# harp_camera_controller_v_1_0.net
KiCad netlist of a schematic drawn in EAGLE
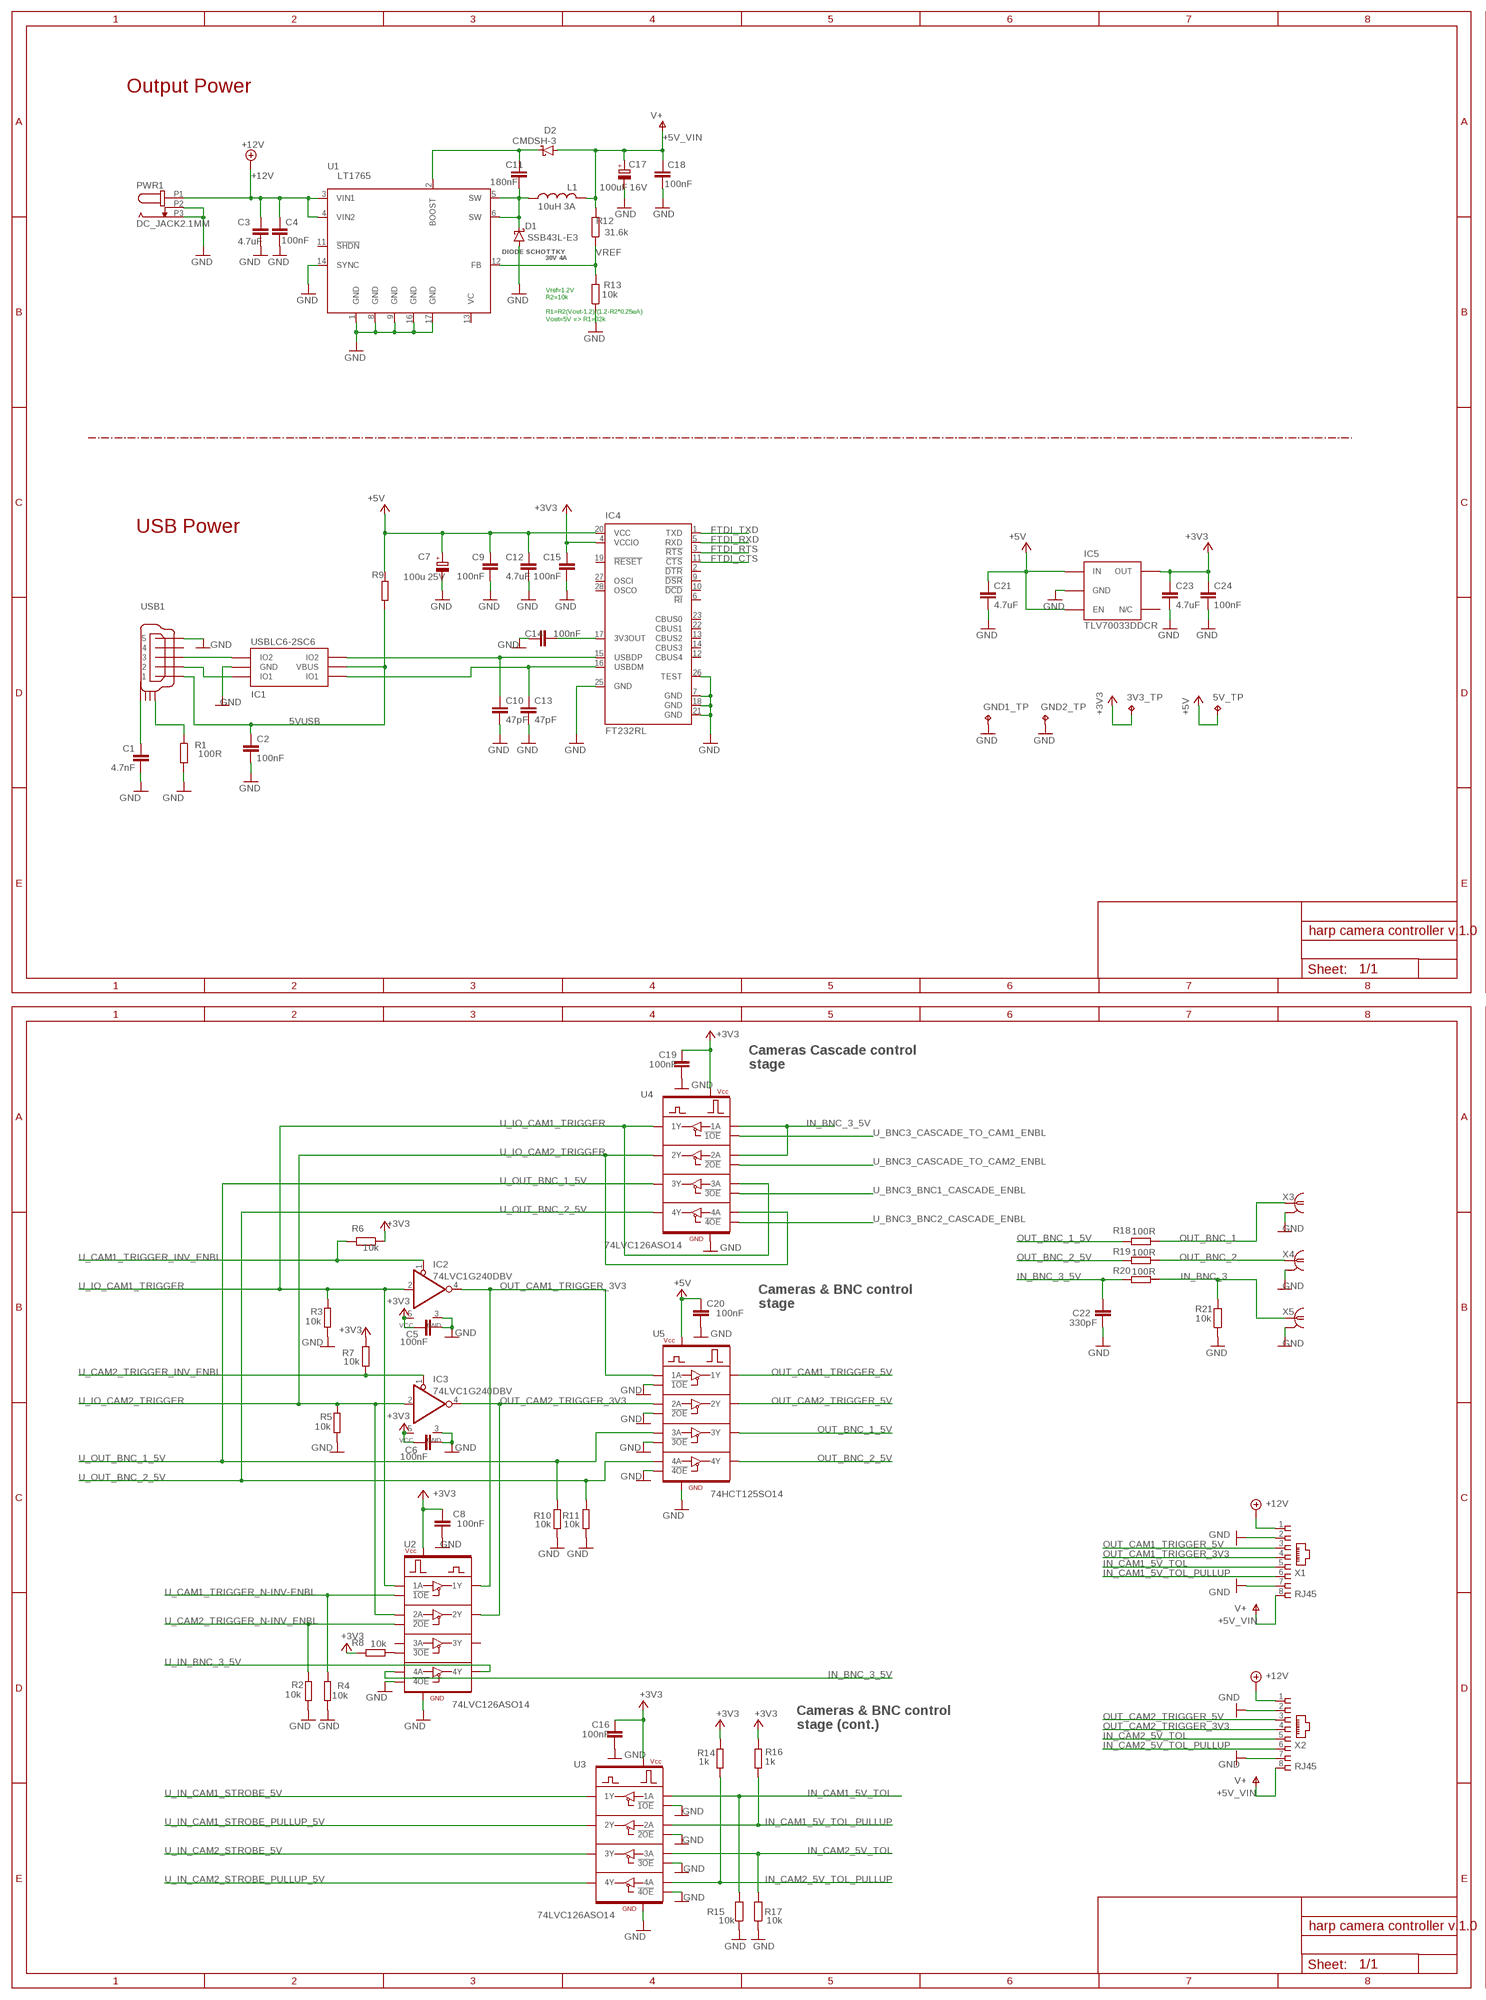
[diagram p0: schematic, sheet 1, part 1 of 2]
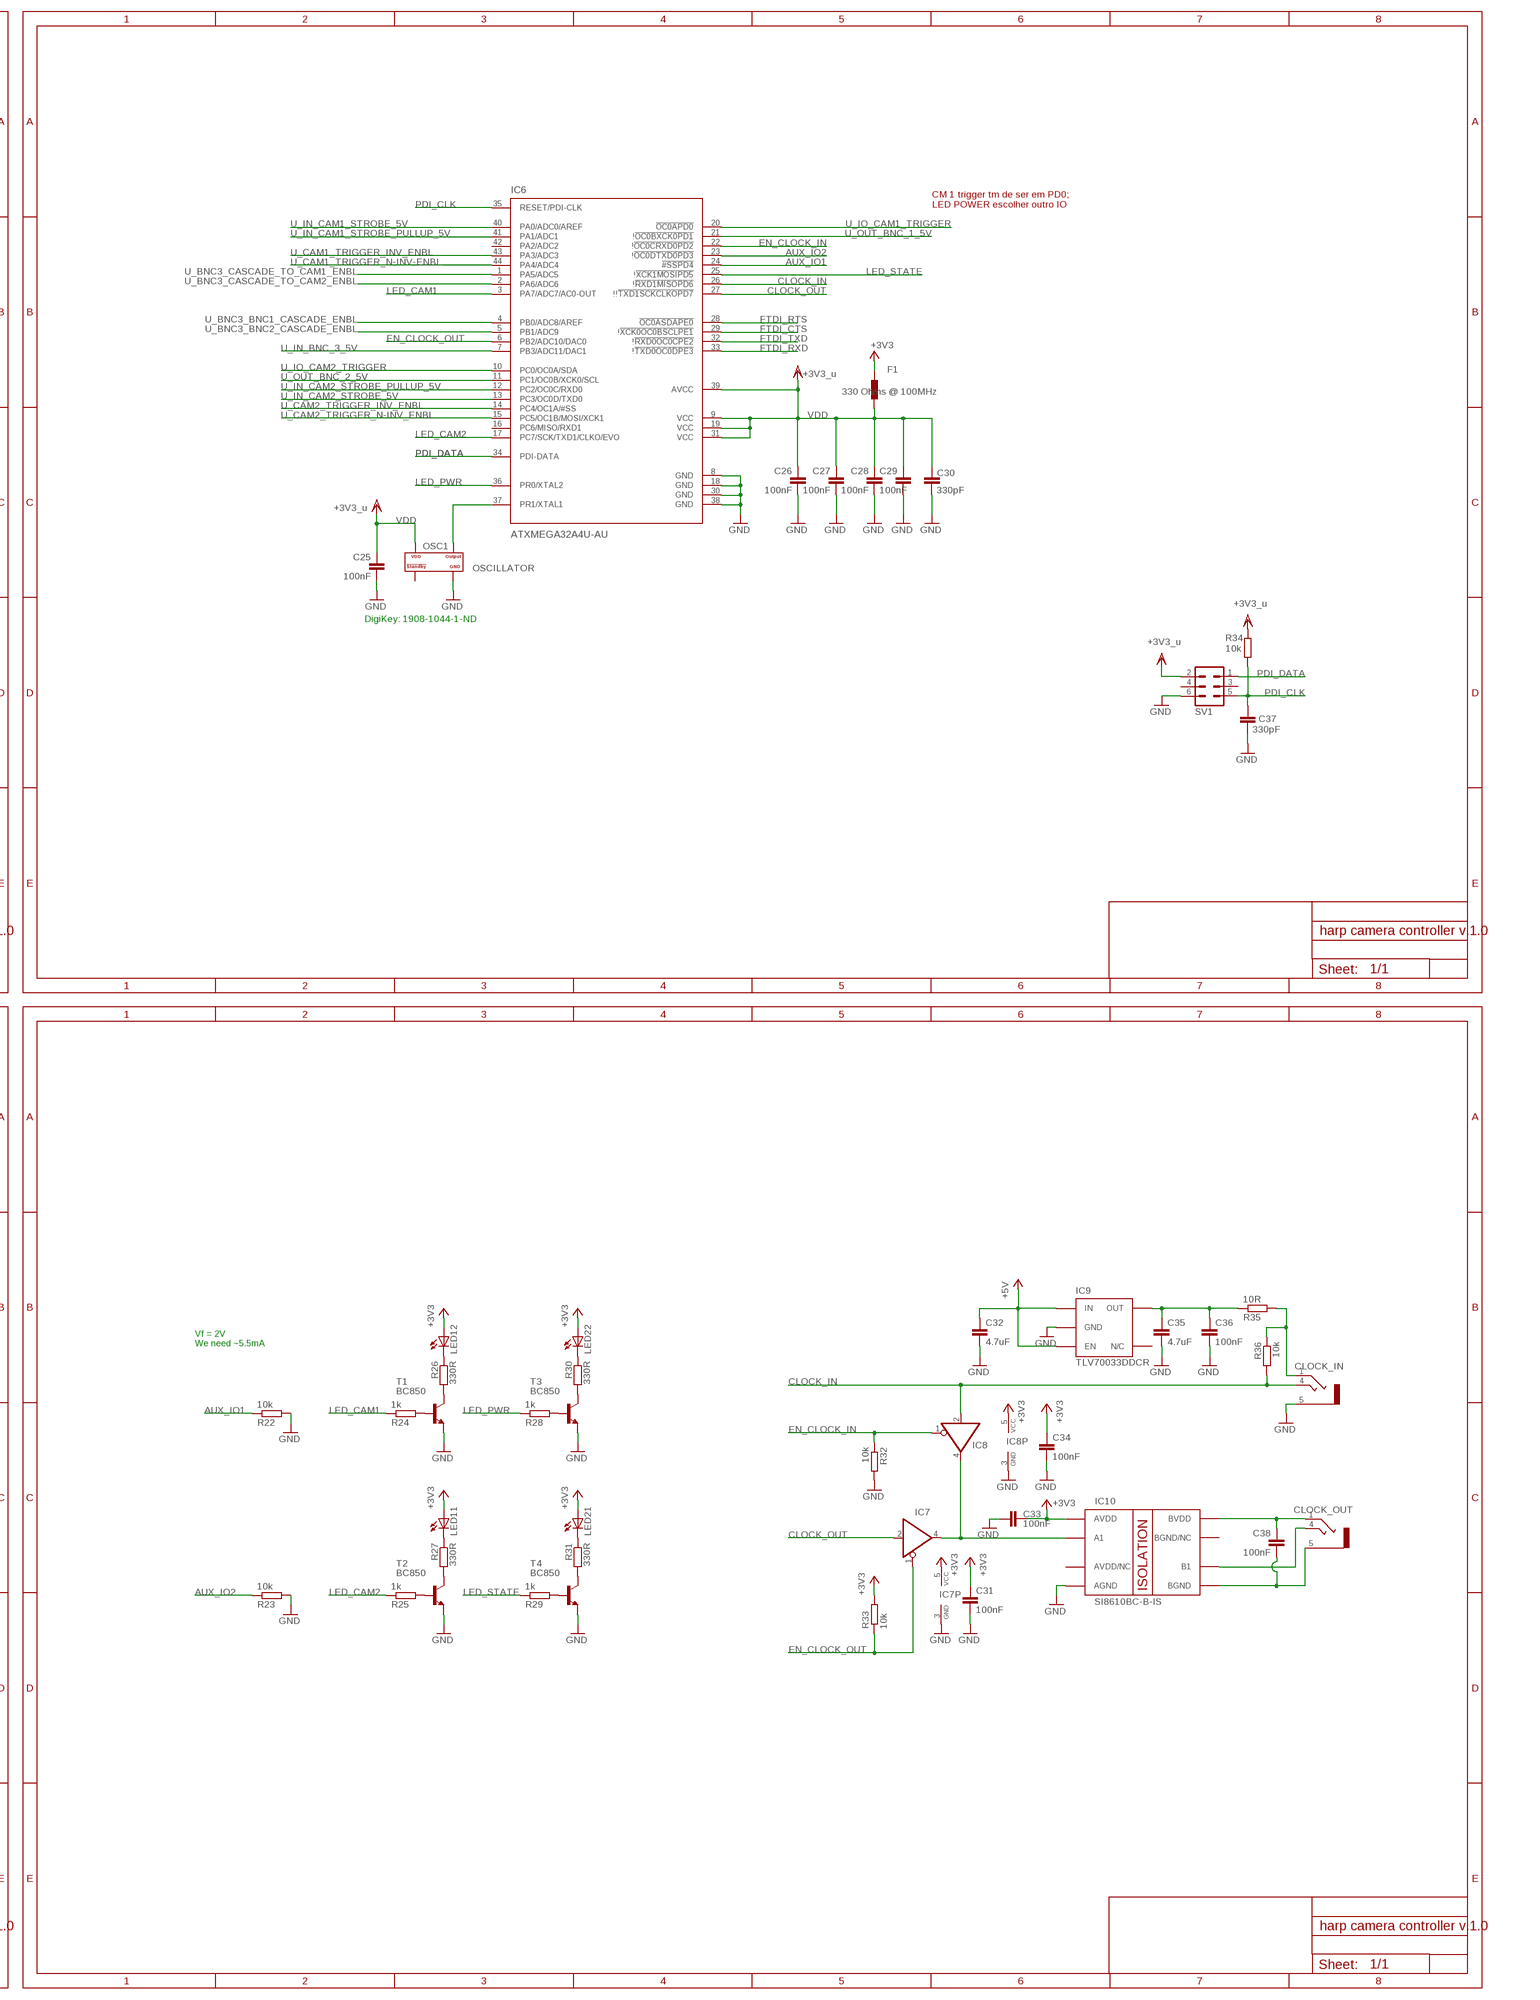
[diagram p1: schematic, sheet 1, part 2 of 2]

(export (version "E")
  (design (tool "Eeschema 10.0.6"))
  (components
    (comp (ref "3V3_TP")
      (value "TPPAD1-13")
      (footprint "eagle-import:P1-13")
      (fields (field (name "MPN") "N.A."))
      (libsource (lib "eagle-import") (part "TPPAD1-13"))
    )
    (comp (ref "5V_TP")
      (value "TPPAD1-13")
      (footprint "eagle-import:P1-13")
      (fields (field (name "MPN") "N.A."))
      (libsource (lib "eagle-import") (part "TPPAD1-13"))
    )
    (comp (ref "C1")
      (value "4.7nF")
      (footprint "eagle-import:C0402")
      (fields (field (name "MPN") "885012205084  "))
      (libsource (lib "eagle-import") (part "C-EUC0402"))
    )
    (comp (ref "C2")
      (value "100nF")
      (footprint "eagle-import:C0402")
      (fields (field (name "MPN") "C1005X7R1H104K050BB"))
      (libsource (lib "eagle-import") (part "C-EUC0402"))
    )
    (comp (ref "C3")
      (value "4.7uF")
      (footprint "eagle-import:C0805")
      (fields (field (name "MPN") "CL21A475KLCLQNC"))
      (libsource (lib "eagle-import") (part "C-EUC0805"))
    )
    (comp (ref "C4")
      (value "100nF")
      (footprint "eagle-import:C0402")
      (fields (field (name "MPN") "C1005X7R1H104K050BB"))
      (libsource (lib "eagle-import") (part "C-EUC0402"))
    )
    (comp (ref "C5")
      (value "100nF")
      (footprint "eagle-import:C0402")
      (fields (field (name "MPN") "C1005X7R1H104K050BB"))
      (libsource (lib "eagle-import") (part "C-EUC0402"))
    )
    (comp (ref "C6")
      (value "100nF")
      (footprint "eagle-import:C0402")
      (fields (field (name "MPN") "C1005X7R1H104K050BB"))
      (libsource (lib "eagle-import") (part "C-EUC0402"))
    )
    (comp (ref "C7")
      (value "100u 25V")
      (footprint "eagle-import:TT2D6")
      (fields (field (name "MPN") "EEU-FM1E101B"))
      (libsource (lib "eagle-import") (part "CPOL-EUTT2D6"))
    )
    (comp (ref "C8")
      (value "100nF")
      (footprint "eagle-import:C0402")
      (fields (field (name "MPN") "C1005X7R1H104K050BB"))
      (libsource (lib "eagle-import") (part "C-EUC0402"))
    )
    (comp (ref "C9")
      (value "100nF")
      (footprint "eagle-import:C0402")
      (fields (field (name "MPN") "C1005X7R1H104K050BB"))
      (libsource (lib "eagle-import") (part "C-EUC0402"))
    )
    (comp (ref "C10")
      (value "47pF")
      (footprint "eagle-import:C0402")
      (fields (field (name "MPN") "04025A470JAT2A"))
      (libsource (lib "eagle-import") (part "C-EUC0402"))
    )
    (comp (ref "C11")
      (value "180nF")
      (footprint "eagle-import:C0603")
      (fields (field (name "MPN") "GCG188R91H184KA01D"))
      (libsource (lib "eagle-import") (part "C-EUC0603"))
    )
    (comp (ref "C12")
      (value "4.7uF")
      (footprint "eagle-import:C0603")
      (fields (field (name "MPN") "C1608X6S1C475K080AC"))
      (libsource (lib "eagle-import") (part "C-EUC0603"))
    )
    (comp (ref "C13")
      (value "47pF")
      (footprint "eagle-import:C0402")
      (fields (field (name "MPN") "04025A470JAT2A"))
      (libsource (lib "eagle-import") (part "C-EUC0402"))
    )
    (comp (ref "C14")
      (value "100nF")
      (footprint "eagle-import:C0402")
      (fields (field (name "MPN") "C1005X7R1H104K050BB"))
      (libsource (lib "eagle-import") (part "C-EUC0402"))
    )
    (comp (ref "C15")
      (value "100nF")
      (footprint "eagle-import:C0402")
      (fields (field (name "MPN") "C1005X7R1H104K050BB"))
      (libsource (lib "eagle-import") (part "C-EUC0402"))
    )
    (comp (ref "C16")
      (value "100nF")
      (footprint "eagle-import:C0402")
      (fields (field (name "MPN") "C1005X7R1H104K050BB"))
      (libsource (lib "eagle-import") (part "C-EUC0402"))
    )
    (comp (ref "C17")
      (value "100uF 16V")
      (footprint "eagle-import:CT7343")
      (fields (field (name "MPN") "T491D107K016AT7280"))
      (libsource (lib "eagle-import") (part "CPOL-EUCT7343"))
    )
    (comp (ref "C18")
      (value "100nF")
      (footprint "eagle-import:C0402")
      (fields (field (name "MPN") "C1005X7R1H104K050BB"))
      (libsource (lib "eagle-import") (part "C-EUC0402"))
    )
    (comp (ref "C19")
      (value "100nF")
      (footprint "eagle-import:C0402")
      (fields (field (name "MPN") "C1005X7R1H104K050BB"))
      (libsource (lib "eagle-import") (part "C-EUC0402"))
    )
    (comp (ref "C20")
      (value "100nF")
      (footprint "eagle-import:C0402")
      (fields (field (name "MPN") "C1005X7R1H104K050BB"))
      (libsource (lib "eagle-import") (part "C-EUC0402"))
    )
    (comp (ref "C21")
      (value "4.7uF")
      (footprint "eagle-import:C0603")
      (fields (field (name "MPN") "C1608X6S1C475K080AC"))
      (libsource (lib "eagle-import") (part "C-EUC0603"))
    )
    (comp (ref "C22")
      (value "330pF")
      (footprint "eagle-import:C0402")
      (fields (field (name "MPN") "C0402C331J5GACTU"))
      (libsource (lib "eagle-import") (part "C-EUC0402"))
    )
    (comp (ref "C23")
      (value "4.7uF")
      (footprint "eagle-import:C0603")
      (fields (field (name "MPN") "C1608X6S1C475K080AC"))
      (libsource (lib "eagle-import") (part "C-EUC0603"))
    )
    (comp (ref "C24")
      (value "100nF")
      (footprint "eagle-import:C0402")
      (fields (field (name "MPN") "C1005X7R1H104K050BB"))
      (libsource (lib "eagle-import") (part "C-EUC0402"))
    )
    (comp (ref "C25")
      (value "100nF")
      (footprint "eagle-import:C0402")
      (fields (field (name "MPN") "C1005X7R1H104K050BB"))
      (libsource (lib "eagle-import") (part "C-EUC0402"))
    )
    (comp (ref "C26")
      (value "100nF")
      (footprint "eagle-import:C0402")
      (fields (field (name "MPN") "C1005X7R1H104K050BB"))
      (libsource (lib "eagle-import") (part "C-EUC0402"))
    )
    (comp (ref "C27")
      (value "100nF")
      (footprint "eagle-import:C0402")
      (fields (field (name "MPN") "C1005X7R1H104K050BB"))
      (libsource (lib "eagle-import") (part "C-EUC0402"))
    )
    (comp (ref "C28")
      (value "100nF")
      (footprint "eagle-import:C0402")
      (fields (field (name "MPN") "C1005X7R1H104K050BB"))
      (libsource (lib "eagle-import") (part "C-EUC0402"))
    )
    (comp (ref "C29")
      (value "100nF")
      (footprint "eagle-import:C0402")
      (fields (field (name "MPN") "C1005X7R1H104K050BB"))
      (libsource (lib "eagle-import") (part "C-EUC0402"))
    )
    (comp (ref "C30")
      (value "330pF")
      (footprint "eagle-import:C0402")
      (fields (field (name "MPN") "C0402C331J5GACTU"))
      (libsource (lib "eagle-import") (part "C-EUC0402"))
    )
    (comp (ref "C31")
      (value "100nF")
      (footprint "eagle-import:C0402")
      (fields (field (name "MPN") "C1005X7R1H104K050BB"))
      (libsource (lib "eagle-import") (part "C-EUC0402"))
    )
    (comp (ref "C32")
      (value "4.7uF")
      (footprint "eagle-import:C0603")
      (fields (field (name "MPN") "C1608X6S1C475K080AC"))
      (libsource (lib "eagle-import") (part "C-EUC0603"))
    )
    (comp (ref "C33")
      (value "100nF")
      (footprint "eagle-import:C0402")
      (fields (field (name "MPN") "C1005X7R1H104K050BB"))
      (libsource (lib "eagle-import") (part "C-EUC0402"))
    )
    (comp (ref "C34")
      (value "100nF")
      (footprint "eagle-import:C0402")
      (fields (field (name "MPN") "C1005X7R1H104K050BB"))
      (libsource (lib "eagle-import") (part "C-EUC0402"))
    )
    (comp (ref "C35")
      (value "4.7uF")
      (footprint "eagle-import:C0603")
      (fields (field (name "MPN") "C1608X6S1C475K080AC"))
      (libsource (lib "eagle-import") (part "C-EUC0603"))
    )
    (comp (ref "C36")
      (value "100nF")
      (footprint "eagle-import:C0402")
      (fields (field (name "MPN") "C1005X7R1H104K050BB"))
      (libsource (lib "eagle-import") (part "C-EUC0402"))
    )
    (comp (ref "C37")
      (value "330pF")
      (footprint "eagle-import:C0402")
      (fields (field (name "MPN") "C0402C331J5GACTU"))
      (libsource (lib "eagle-import") (part "C-EUC0402"))
    )
    (comp (ref "C38")
      (value "100nF")
      (footprint "eagle-import:C0402")
      (fields (field (name "MPN") "C1005X7R1H104K050BB"))
      (libsource (lib "eagle-import") (part "C-EUC0402"))
    )
    (comp (ref "CLOCK_IN")
      (value "CLCK_JACK")
      (footprint "eagle-import:35RASMT2BHNTRX")
      (fields (field (name "MPN") "35RASMT2BHNTRX"))
      (libsource (lib "eagle-import") (part "STEREO_JACK"))
    )
    (comp (ref "CLOCK_OUT")
      (value "CLCK_JACK")
      (footprint "eagle-import:35RASMT2BHNTRX")
      (fields (field (name "MPN") "35RASMT2BHNTRX"))
      (libsource (lib "eagle-import") (part "STEREO_JACK"))
    )
    (comp (ref "D1")
      (value "SSB43L-E3")
      (footprint "eagle-import:SMB")
      (fields (field (name "MPN") "SSB43L-E3/52T"))
      (libsource (lib "eagle-import") (part "SCHOTTKY-DIODE"))
    )
    (comp (ref "D2")
      (value "CMDSH-3")
      (footprint "eagle-import:SOD323-R")
      (libsource (lib "eagle-import") (part "SCHOTTKY-DIODESOD323"))
    )
    (comp (ref "F1")
      (value "330 Ohms @ 100MHz")
      (footprint "eagle-import:R0603")
      (fields (field (name "MPN") "BLM18SG331TN1D"))
      (libsource (lib "eagle-import") (part "BLM15HF0603"))
    )
    (comp (ref "GND1_TP")
      (value "TPPAD1-13")
      (footprint "eagle-import:P1-13")
      (fields (field (name "MPN") "N.A."))
      (libsource (lib "eagle-import") (part "TPPAD1-13"))
    )
    (comp (ref "GND2_TP")
      (value "TPPAD1-13")
      (footprint "eagle-import:P1-13")
      (fields (field (name "MPN") "N.A."))
      (libsource (lib "eagle-import") (part "TPPAD1-13"))
    )
    (comp (ref "IC1")
      (value "USBLC6-2SC6")
      (footprint "eagle-import:SOT23-6L")
      (libsource (lib "eagle-import") (part "USBLC6-2"))
    )
    (comp (ref "IC2")
      (value "74LVC1G240DBV")
      (footprint "eagle-import:SOT23-5")
      (fields (field (name "MPN") "SN74LVC1G240DBVR"))
      (libsource (lib "eagle-import") (part "74LVC1G240DBV"))
    )
    (comp (ref "IC3")
      (value "74LVC1G240DBV")
      (footprint "eagle-import:SOT23-5")
      (fields (field (name "MPN") "SN74LVC1G240DBVR"))
      (libsource (lib "eagle-import") (part "74LVC1G240DBV"))
    )
    (comp (ref "IC4")
      (value "FT232RL")
      (footprint "eagle-import:SSOP28")
      (fields (field (name "MPN") "FT232RL-REEL"))
      (libsource (lib "eagle-import") (part "FT232RL"))
    )
    (comp (ref "IC5")
      (value "TLV70033DDCR")
      (footprint "eagle-import:TSOT23-5")
      (libsource (lib "eagle-import") (part "TLV700XX"))
    )
    (comp (ref "IC6")
      (value "ATXMEGA32A4U-AU")
      (footprint "eagle-import:QFP80P1200X1200X120-44N")
      (fields (field (name "MPN") "ATXMEGA32A4U-AUR"))
      (libsource (lib "eagle-import") (part "AT-XMEGA-XXA4-AU"))
    )
    (comp (ref "IC7")
      (value "SN74LVC1G125DBVT")
      (footprint "eagle-import:SOT23-5")
      (fields
        (field (name "DIGIKEY_PN") "296-26595-1-ND")
        (field (name "MOUSER_PN") "595-SN74LVC1G125DBVT")
        (field (name "MPN") "SN74LVC1G125DBVT")
      )
      (libsource (lib "eagle-import") (part "741G125DBVAHC"))
    )
    (comp (ref "IC8")
      (value "SN74LVC1G125DBVT")
      (footprint "eagle-import:SOT23-5")
      (fields
        (field (name "DIGIKEY_PN") "296-26595-1-ND")
        (field (name "MOUSER_PN") "595-SN74LVC1G125DBVT")
        (field (name "MPN") "SN74LVC1G125DBVT")
      )
      (libsource (lib "eagle-import") (part "741G125DBVAHC"))
    )
    (comp (ref "IC9")
      (value "TLV70033DDCR")
      (footprint "eagle-import:TSOT23-5")
      (libsource (lib "eagle-import") (part "TLV700XX"))
    )
    (comp (ref "IC10")
      (value "SI8610BC-B-IS")
      (footprint "eagle-import:SO-08")
      (fields (field (name "MPN") "SI8610EC-B-IS"))
      (libsource (lib "eagle-import") (part "SI8610"))
    )
    (comp (ref "L1")
      (value "10uH 3A")
      (footprint "eagle-import:L_IHLP_PADS")
      (fields (field (name "MPN") "IHLP2525CZER100M01"))
      (libsource (lib "eagle-import") (part "L_IHLP2525CZER100M01"))
    )
    (comp (ref "LED1")
      (value "RED_LEDs")
      (footprint "eagle-import:569-011X-X00_LED_ARRAY")
      (fields (field (name "MPN") "5690-111-100F"))
      (libsource (lib "eagle-import") (part "LED_2X_VERTICAL"))
    )
    (comp (ref "LED2")
      (value "RED_LEDs")
      (footprint "eagle-import:569-011X-X00_LED_ARRAY")
      (fields (field (name "MPN") "5690-111-100F"))
      (libsource (lib "eagle-import") (part "LED_2X_VERTICAL"))
    )
    (comp (ref "OSC1")
      (value "OSCILLATOR")
      (footprint "eagle-import:OSCILLATOR_3.2X2.5")
      (fields (field (name "MPN") "O 32,0-JT32C-A-K-3,3-LF"))
      (libsource (lib "eagle-import") (part "OSCILLATOR"))
    )
    (comp (ref "PWR1")
      (value "DC_JACK2.1MM")
      (footprint "eagle-import:DC_POWER_INPUT_2.1MM")
      (fields (field (name "MPN") "163-179PH-EX"))
      (libsource (lib "eagle-import") (part "DC_JACK2.1MM"))
    )
    (comp (ref "R1")
      (value "100R")
      (footprint "eagle-import:R0603")
      (fields (field (name "MPN") "ERJ-3EKF1000V"))
      (libsource (lib "eagle-import") (part "R-EU_R0603"))
    )
    (comp (ref "R2")
      (value "10k")
      (footprint "eagle-import:R0402")
      (fields (field (name "MPN") "CRCW040210K0FKED"))
      (libsource (lib "eagle-import") (part "R-EU_R0402"))
    )
    (comp (ref "R3")
      (value "10k")
      (footprint "eagle-import:R0402")
      (fields (field (name "MPN") "CRCW040210K0FKED"))
      (libsource (lib "eagle-import") (part "R-EU_R0402"))
    )
    (comp (ref "R4")
      (value "10k")
      (footprint "eagle-import:R0402")
      (fields (field (name "MPN") "CRCW040210K0FKED"))
      (libsource (lib "eagle-import") (part "R-EU_R0402"))
    )
    (comp (ref "R5")
      (value "10k")
      (footprint "eagle-import:R0402")
      (fields (field (name "MPN") "CRCW040210K0FKED"))
      (libsource (lib "eagle-import") (part "R-EU_R0402"))
    )
    (comp (ref "R6")
      (value "10k")
      (footprint "eagle-import:R0402")
      (fields (field (name "MPN") "CRCW040210K0FKED"))
      (libsource (lib "eagle-import") (part "R-EU_R0402"))
    )
    (comp (ref "R7")
      (value "10k")
      (footprint "eagle-import:R0402")
      (fields (field (name "MPN") "CRCW040210K0FKED"))
      (libsource (lib "eagle-import") (part "R-EU_R0402"))
    )
    (comp (ref "R8")
      (value "10k")
      (footprint "eagle-import:R0402")
      (fields (field (name "MPN") "CRCW040210K0FKED"))
      (libsource (lib "eagle-import") (part "R-EU_R0402"))
    )
    (comp (ref "R9")
      (value "40R@100MHz")
      (footprint "eagle-import:R0805")
      (fields (field (name "MPN") "MI0805K400R-10"))
      (libsource (lib "eagle-import") (part "R-EU_R0805"))
    )
    (comp (ref "R10")
      (value "10k")
      (footprint "eagle-import:R0402")
      (fields (field (name "MPN") "CRCW040210K0FKED"))
      (libsource (lib "eagle-import") (part "R-EU_R0402"))
    )
    (comp (ref "R11")
      (value "10k")
      (footprint "eagle-import:R0402")
      (fields (field (name "MPN") "CRCW040210K0FKED"))
      (libsource (lib "eagle-import") (part "R-EU_R0402"))
    )
    (comp (ref "R12")
      (value "31.6k")
      (footprint "eagle-import:R0402")
      (fields (field (name "MPN") "RC0402FR-0740K2L"))
      (libsource (lib "eagle-import") (part "R-EU_R0402"))
    )
    (comp (ref "R13")
      (value "10k")
      (footprint "eagle-import:R0402")
      (fields (field (name "MPN") "CRCW040210K0FKED"))
      (libsource (lib "eagle-import") (part "R-EU_R0402"))
    )
    (comp (ref "R14")
      (value "1k")
      (footprint "eagle-import:R0402")
      (fields (field (name "MPN") "CRCW04021K00FKEDC"))
      (libsource (lib "eagle-import") (part "R-EU_R0402"))
    )
    (comp (ref "R15")
      (value "10k")
      (footprint "eagle-import:R0402")
      (fields (field (name "MPN") "CRCW040210K0FKED"))
      (libsource (lib "eagle-import") (part "R-EU_R0402"))
    )
    (comp (ref "R16")
      (value "1k")
      (footprint "eagle-import:R0402")
      (fields (field (name "MPN") "CRCW04021K00FKEDC"))
      (libsource (lib "eagle-import") (part "R-EU_R0402"))
    )
    (comp (ref "R17")
      (value "10k")
      (footprint "eagle-import:R0402")
      (fields (field (name "MPN") "CRCW040210K0FKED"))
      (libsource (lib "eagle-import") (part "R-EU_R0402"))
    )
    (comp (ref "R18")
      (value "100R")
      (footprint "eagle-import:R0603")
      (fields (field (name "MPN") "ERJ-3EKF1000V"))
      (libsource (lib "eagle-import") (part "R-EU_R0603"))
    )
    (comp (ref "R19")
      (value "100R")
      (footprint "eagle-import:R0603")
      (fields (field (name "MPN") "ERJ-3EKF1000V"))
      (libsource (lib "eagle-import") (part "R-EU_R0603"))
    )
    (comp (ref "R20")
      (value "100R")
      (footprint "eagle-import:R0603")
      (fields (field (name "MPN") "ERJ-3EKF1000V"))
      (libsource (lib "eagle-import") (part "R-EU_R0603"))
    )
    (comp (ref "R21")
      (value "10k")
      (footprint "eagle-import:R0402")
      (fields (field (name "MPN") "CRCW040210K0FKED"))
      (libsource (lib "eagle-import") (part "R-EU_R0402"))
    )
    (comp (ref "R22")
      (value "10k")
      (footprint "eagle-import:R0402")
      (fields (field (name "MPN") "CRCW040210K0FKED"))
      (libsource (lib "eagle-import") (part "R-EU_R0402"))
    )
    (comp (ref "R23")
      (value "10k")
      (footprint "eagle-import:R0402")
      (fields (field (name "MPN") "CRCW040210K0FKED"))
      (libsource (lib "eagle-import") (part "R-EU_R0402"))
    )
    (comp (ref "R24")
      (value "1k")
      (footprint "eagle-import:R0402")
      (fields (field (name "MPN") "CRCW04021K00FKEDC"))
      (libsource (lib "eagle-import") (part "R-EU_R0402"))
    )
    (comp (ref "R25")
      (value "1k")
      (footprint "eagle-import:R0402")
      (fields (field (name "MPN") "CRCW04021K00FKEDC"))
      (libsource (lib "eagle-import") (part "R-EU_R0402"))
    )
    (comp (ref "R26")
      (value "330R")
      (footprint "eagle-import:R0402")
      (fields (field (name "MPN") "RC0402FR-07330RL "))
      (libsource (lib "eagle-import") (part "R-EU_R0402"))
    )
    (comp (ref "R27")
      (value "330R")
      (footprint "eagle-import:R0402")
      (fields (field (name "MPN") "RC0402FR-07330RL "))
      (libsource (lib "eagle-import") (part "R-EU_R0402"))
    )
    (comp (ref "R28")
      (value "1k")
      (footprint "eagle-import:R0402")
      (fields (field (name "MPN") "CRCW04021K00FKEDC"))
      (libsource (lib "eagle-import") (part "R-EU_R0402"))
    )
    (comp (ref "R29")
      (value "1k")
      (footprint "eagle-import:R0402")
      (fields (field (name "MPN") "CRCW04021K00FKEDC"))
      (libsource (lib "eagle-import") (part "R-EU_R0402"))
    )
    (comp (ref "R30")
      (value "330R")
      (footprint "eagle-import:R0402")
      (fields (field (name "MPN") "RC0402FR-07330RL "))
      (libsource (lib "eagle-import") (part "R-EU_R0402"))
    )
    (comp (ref "R31")
      (value "330R")
      (footprint "eagle-import:R0402")
      (fields (field (name "MPN") "RC0402FR-07330RL "))
      (libsource (lib "eagle-import") (part "R-EU_R0402"))
    )
    (comp (ref "R32")
      (value "10k")
      (footprint "eagle-import:R0402")
      (fields (field (name "MPN") "CRCW040210K0FKED"))
      (libsource (lib "eagle-import") (part "R-EU_R0402"))
    )
    (comp (ref "R33")
      (value "10k")
      (footprint "eagle-import:R0402")
      (fields (field (name "MPN") "CRCW040210K0FKED"))
      (libsource (lib "eagle-import") (part "R-EU_R0402"))
    )
    (comp (ref "R34")
      (value "10k")
      (footprint "eagle-import:R0402")
      (fields (field (name "MPN") "CRCW040210K0FKED"))
      (libsource (lib "eagle-import") (part "R-EU_R0402"))
    )
    (comp (ref "R35")
      (value "10R")
      (footprint "eagle-import:R0402")
      (fields (field (name "MPN") "CRCW040210R0FKEDC"))
      (libsource (lib "eagle-import") (part "R-EU_R0402"))
    )
    (comp (ref "R36")
      (value "10k")
      (footprint "eagle-import:R0402")
      (fields (field (name "MPN") "CRCW040210K0FKED"))
      (libsource (lib "eagle-import") (part "R-EU_R0402"))
    )
    (comp (ref "SV1")
      (value "PROG HEADER")
      (footprint "eagle-import:MA03-2")
      (fields (field (name "MPN") "61300621121"))
      (libsource (lib "eagle-import") (part "MA03-2"))
    )
    (comp (ref "T1")
      (value "BC850")
      (footprint "eagle-import:SOT23")
      (fields (field (name "MPN") "BC850C,215"))
      (libsource (lib "eagle-import") (part "BC850"))
    )
    (comp (ref "T2")
      (value "BC850")
      (footprint "eagle-import:SOT23")
      (fields (field (name "MPN") "BC850C,215"))
      (libsource (lib "eagle-import") (part "BC850"))
    )
    (comp (ref "T3")
      (value "BC850")
      (footprint "eagle-import:SOT23")
      (fields (field (name "MPN") "BC850C,215"))
      (libsource (lib "eagle-import") (part "BC850"))
    )
    (comp (ref "T4")
      (value "BC850")
      (footprint "eagle-import:SOT23")
      (fields (field (name "MPN") "BC850C,215"))
      (libsource (lib "eagle-import") (part "BC850"))
    )
    (comp (ref "U1")
      (value "LT1765")
      (footprint "eagle-import:TSSOP16EXP")
      (fields (field (name "MPN") "LT1765EFE#PBF"))
      (libsource (lib "eagle-import") (part "LT1765"))
    )
    (comp (ref "U2")
      (value "74LVC126ASO14")
      (footprint "eagle-import:SO14")
      (fields (field (name "MPN") "74LVC126AD,118  "))
      (libsource (lib "eagle-import") (part "74LVC126ASO14"))
    )
    (comp (ref "U3")
      (value "74LVC126ASO14")
      (footprint "eagle-import:SO14")
      (fields (field (name "MPN") "74LVC126AD,118  "))
      (libsource (lib "eagle-import") (part "74LVC126ASO14"))
    )
    (comp (ref "U4")
      (value "74LVC126ASO14")
      (footprint "eagle-import:SO14")
      (fields (field (name "MPN") "74LVC126AD,118  "))
      (libsource (lib "eagle-import") (part "74LVC126ASO14"))
    )
    (comp (ref "U5")
      (value "74HCT125SO14")
      (footprint "eagle-import:SO14")
      (fields (field (name "MPN") "74HCT125D,653"))
      (libsource (lib "eagle-import") (part "74HCT125SO14"))
    )
    (comp (ref "USB1")
      (value "mini USB")
      (footprint "eagle-import:240-0002-1")
      (fields (field (name "MPN") "UX60-MB-5S8 "))
      (libsource (lib "eagle-import") (part "USB_MINI_B"))
    )
    (comp (ref "X1")
      (value "RJ45")
      (footprint "eagle-import:RJ45-NO-SHIELD")
      (fields (field (name "MPN") "215877-1"))
      (libsource (lib "eagle-import") (part "RJ45"))
    )
    (comp (ref "X2")
      (value "RJ45")
      (footprint "eagle-import:RJ45-NO-SHIELD")
      (fields (field (name "MPN") "215877-1"))
      (libsource (lib "eagle-import") (part "RJ45"))
    )
    (comp (ref "X3")
      (value "BNC plug")
      (footprint "eagle-import:0731000105")
      (fields (field (name "MPN") "73100-0105"))
      (libsource (lib "eagle-import") (part "BNC_0731000105"))
    )
    (comp (ref "X4")
      (value "BNC plug")
      (footprint "eagle-import:0731000105")
      (fields (field (name "MPN") "73100-0105"))
      (libsource (lib "eagle-import") (part "BNC_0731000105"))
    )
    (comp (ref "X5")
      (value "BNC plug")
      (footprint "eagle-import:0731000105")
      (fields (field (name "MPN") "73100-0105"))
      (libsource (lib "eagle-import") (part "BNC_0731000105"))
    )
  )
  (nets
    (net (code "1") (name "+3V3") (class "Default")
      (node (ref "3V3_TP") (pin "TP") (pinfunction "TP_TP") (pintype "input"))
      (node (ref "C15") (pin "1") (pinfunction "1_1") (pintype "passive"))
      (node (ref "C16") (pin "1") (pinfunction "1_1") (pintype "passive"))
      (node (ref "C19") (pin "1") (pinfunction "1_1") (pintype "passive"))
      (node (ref "C23") (pin "1") (pinfunction "1_1") (pintype "passive"))
      (node (ref "C24") (pin "1") (pinfunction "1_1") (pintype "passive"))
      (node (ref "C31") (pin "1") (pinfunction "1_1") (pintype "passive"))
      (node (ref "C33") (pin "1") (pinfunction "1_1") (pintype "passive"))
      (node (ref "C34") (pin "1") (pinfunction "1_1") (pintype "passive"))
      (node (ref "C5") (pin "1") (pinfunction "1_1") (pintype "passive"))
      (node (ref "C6") (pin "1") (pinfunction "1_1") (pintype "passive"))
      (node (ref "C8") (pin "1") (pinfunction "1_1") (pintype "passive"))
      (node (ref "F1") (pin "2") (pinfunction "2_2") (pintype "passive"))
      (node (ref "IC10") (pin "1") (pinfunction "AVDD_1") (pintype "bidirectional"))
      (node (ref "IC2") (pin "5") (pinfunction "VCC_5") (pintype "input"))
      (node (ref "IC3") (pin "5") (pinfunction "VCC_5") (pintype "input"))
      (node (ref "IC4") (pin "4") (pinfunction "VCCIO_4") (pintype "input"))
      (node (ref "IC5") (pin "5") (pinfunction "OUT_5") (pintype "bidirectional"))
      (node (ref "IC7") (pin "5") (pinfunction "VCC_5") (pintype "power_in"))
      (node (ref "IC8") (pin "5") (pinfunction "VCC_5") (pintype "power_in"))
      (node (ref "LED1") (pin "A1") (pinfunction "A_A1") (pintype "passive"))
      (node (ref "LED1") (pin "A2") (pinfunction "A_A2") (pintype "passive"))
      (node (ref "LED2") (pin "A1") (pinfunction "A_A1") (pintype "passive"))
      (node (ref "LED2") (pin "A2") (pinfunction "A_A2") (pintype "passive"))
      (node (ref "R14") (pin "1") (pinfunction "1_1") (pintype "passive"))
      (node (ref "R16") (pin "1") (pinfunction "1_1") (pintype "passive"))
      (node (ref "R33") (pin "2") (pinfunction "2_2") (pintype "passive"))
      (node (ref "R6") (pin "1") (pinfunction "1_1") (pintype "passive"))
      (node (ref "R7") (pin "1") (pinfunction "1_1") (pintype "passive"))
      (node (ref "R8") (pin "1") (pinfunction "1_1") (pintype "passive"))
      (node (ref "U2") (pin "14") (pinfunction "VCC_14") (pintype "input"))
      (node (ref "U3") (pin "14") (pinfunction "VCC_14") (pintype "input"))
      (node (ref "U4") (pin "14") (pinfunction "VCC_14") (pintype "input"))
    )
    (net (code "2") (name "+3V3_u") (class "Default")
      (node (ref "C25") (pin "1") (pinfunction "1_1") (pintype "passive"))
      (node (ref "C26") (pin "1") (pinfunction "1_1") (pintype "passive"))
      (node (ref "C27") (pin "1") (pinfunction "1_1") (pintype "passive"))
      (node (ref "C28") (pin "1") (pinfunction "1_1") (pintype "passive"))
      (node (ref "C29") (pin "1") (pinfunction "1_1") (pintype "passive"))
      (node (ref "C30") (pin "1") (pinfunction "1_1") (pintype "passive"))
      (node (ref "F1") (pin "1") (pinfunction "1_1") (pintype "passive"))
      (node (ref "IC6") (pin "19") (pinfunction "VCC_19") (pintype "power_in"))
      (node (ref "IC6") (pin "31") (pinfunction "VCC_31") (pintype "power_in"))
      (node (ref "IC6") (pin "39") (pinfunction "AVCC_39") (pintype "power_in"))
      (node (ref "IC6") (pin "9") (pinfunction "VCC_9") (pintype "power_in"))
      (node (ref "OSC1") (pin "P$4") (pinfunction "VDD_P$4") (pintype "passive"))
      (node (ref "R34") (pin "2") (pinfunction "2_2") (pintype "passive"))
      (node (ref "SV1") (pin "2") (pinfunction "2_2") (pintype "passive"))
    )
    (net (code "3") (name "+5V") (class "Default")
      (node (ref "5V_TP") (pin "TP") (pinfunction "TP_TP") (pintype "input"))
      (node (ref "C12") (pin "1") (pinfunction "1_1") (pintype "passive"))
      (node (ref "C20") (pin "1") (pinfunction "1_1") (pintype "passive"))
      (node (ref "C21") (pin "1") (pinfunction "1_1") (pintype "passive"))
      (node (ref "C32") (pin "1") (pinfunction "1_1") (pintype "passive"))
      (node (ref "C7") (pin "+") (pinfunction "+_+") (pintype "passive"))
      (node (ref "C9") (pin "1") (pinfunction "1_1") (pintype "passive"))
      (node (ref "IC4") (pin "20") (pinfunction "VCC_20") (pintype "input"))
      (node (ref "IC5") (pin "1") (pinfunction "IN_1") (pintype "bidirectional"))
      (node (ref "IC5") (pin "3") (pinfunction "EN_3") (pintype "bidirectional"))
      (node (ref "IC9") (pin "1") (pinfunction "IN_1") (pintype "bidirectional"))
      (node (ref "IC9") (pin "3") (pinfunction "EN_3") (pintype "bidirectional"))
      (node (ref "R9") (pin "1") (pinfunction "1_1") (pintype "passive"))
      (node (ref "U5") (pin "14") (pinfunction "VCC_14") (pintype "input"))
    )
    (net (code "4") (name "+12V") (class "Default")
      (node (ref "C3") (pin "1") (pinfunction "1_1") (pintype "passive"))
      (node (ref "C4") (pin "1") (pinfunction "1_1") (pintype "passive"))
      (node (ref "PWR1") (pin "P1") (pinfunction "1_P1") (pintype "passive"))
      (node (ref "U1") (pin "3") (pinfunction "VIN1_3") (pintype "bidirectional"))
      (node (ref "U1") (pin "4") (pinfunction "VIN2_4") (pintype "bidirectional"))
      (node (ref "X1") (pin "1") (pinfunction "1_1") (pintype "passive"))
      (node (ref "X2") (pin "1") (pinfunction "1_1") (pintype "passive"))
    )
    (net (code "5") (name "/5VUSB") (class "Default")
      (node (ref "C2") (pin "1") (pinfunction "1_1") (pintype "passive"))
      (node (ref "IC1") (pin "P$5") (pinfunction "VBUS_P$5") (pintype "bidirectional"))
      (node (ref "R9") (pin "2") (pinfunction "2_2") (pintype "passive"))
      (node (ref "USB1") (pin "P$1") (pinfunction "1_P$1") (pintype "bidirectional"))
    )
    (net (code "6") (name "/AUX_IO1") (class "Default")
      (node (ref "IC6") (pin "24") (pinfunction "~{#SSPD4}_24") (pintype "bidirectional"))
      (node (ref "R22") (pin "1") (pinfunction "1_1") (pintype "passive"))
    )
    (net (code "7") (name "/AUX_IO2") (class "Default")
      (node (ref "IC6") (pin "23") (pinfunction "~OC0DTXD0PD3_23") (pintype "bidirectional"))
      (node (ref "R23") (pin "1") (pinfunction "1_1") (pintype "passive"))
    )
    (net (code "8") (name "/CLOCK_IN") (class "Default")
      (node (ref "CLOCK_IN") (pin "4") (pinfunction "4_4") (pintype "passive"))
      (node (ref "IC6") (pin "26") (pinfunction "~RXD1MISOPD6_26") (pintype "bidirectional"))
      (node (ref "IC8") (pin "2") (pinfunction "I_2") (pintype "input"))
      (node (ref "R36") (pin "2") (pinfunction "2_2") (pintype "passive"))
    )
    (net (code "9") (name "/CLOCK_OUT") (class "Default")
      (node (ref "IC6") (pin "27") (pinfunction "~~{TXD1SCKCLKOPD7}_27") (pintype "bidirectional"))
      (node (ref "IC7") (pin "2") (pinfunction "I_2") (pintype "input"))
    )
    (net (code "10") (name "/EN_CLOCK_IN") (class "Default")
      (node (ref "IC6") (pin "22") (pinfunction "~OC0CRXD0PD2_22") (pintype "bidirectional"))
      (node (ref "IC8") (pin "1") (pinfunction "OE_1") (pintype "input"))
      (node (ref "R32") (pin "1") (pinfunction "1_1") (pintype "passive"))
    )
    (net (code "11") (name "/EN_CLOCK_OUT") (class "Default")
      (node (ref "IC6") (pin "6") (pinfunction "PB2/ADC10/DAC0_6") (pintype "bidirectional"))
      (node (ref "IC7") (pin "1") (pinfunction "OE_1") (pintype "input"))
      (node (ref "R33") (pin "1") (pinfunction "1_1") (pintype "passive"))
    )
    (net (code "12") (name "/FTDI_CTS") (class "Default")
      (node (ref "IC4") (pin "11") (pinfunction "~{CTS}_11") (pintype "input"))
      (node (ref "IC6") (pin "29") (pinfunction "~XCK0OC0BSCLPE1_29") (pintype "bidirectional"))
    )
    (net (code "13") (name "/FTDI_RTS") (class "Default")
      (node (ref "IC4") (pin "3") (pinfunction "~{RTS}_3") (pintype "output"))
      (node (ref "IC6") (pin "28") (pinfunction "~{OC0ASDAPE0}_28") (pintype "bidirectional"))
    )
    (net (code "14") (name "/FTDI_RXD") (class "Default")
      (node (ref "IC4") (pin "5") (pinfunction "RXD_5") (pintype "input"))
      (node (ref "IC6") (pin "33") (pinfunction "~TXD0OC0DPE3_33") (pintype "bidirectional"))
    )
    (net (code "15") (name "/FTDI_TXD") (class "Default")
      (node (ref "IC4") (pin "1") (pinfunction "TXD_1") (pintype "output"))
      (node (ref "IC6") (pin "32") (pinfunction "~RXD0OC0CPE2_32") (pintype "bidirectional"))
    )
    (net (code "16") (name "/IN_BNC_3") (class "Default")
      (node (ref "R20") (pin "1") (pinfunction "1_1") (pintype "passive"))
      (node (ref "R21") (pin "2") (pinfunction "2_2") (pintype "passive"))
      (node (ref "X5") (pin "1") (pinfunction "1_1") (pintype "passive"))
    )
    (net (code "17") (name "/IN_BNC_3_5V") (class "Default")
      (node (ref "C22") (pin "1") (pinfunction "1_1") (pintype "passive"))
      (node (ref "R20") (pin "2") (pinfunction "2_2") (pintype "passive"))
      (node (ref "U2") (pin "12") (pinfunction "4A_12") (pintype "bidirectional"))
      (node (ref "U4") (pin "2") (pinfunction "1A_2") (pintype "bidirectional"))
      (node (ref "U4") (pin "5") (pinfunction "2A_5") (pintype "bidirectional"))
    )
    (net (code "18") (name "/IN_CAM1_5V_TOL") (class "Default")
      (node (ref "R15") (pin "2") (pinfunction "2_2") (pintype "passive"))
      (node (ref "U3") (pin "2") (pinfunction "1A_2") (pintype "bidirectional"))
      (node (ref "X1") (pin "5") (pinfunction "5_5") (pintype "passive"))
    )
    (net (code "19") (name "/IN_CAM1_5V_TOL_PULLUP") (class "Default")
      (node (ref "R16") (pin "2") (pinfunction "2_2") (pintype "passive"))
      (node (ref "U3") (pin "5") (pinfunction "2A_5") (pintype "bidirectional"))
      (node (ref "X1") (pin "6") (pinfunction "6_6") (pintype "passive"))
    )
    (net (code "20") (name "/IN_CAM2_5V_TOL") (class "Default")
      (node (ref "R17") (pin "2") (pinfunction "2_2") (pintype "passive"))
      (node (ref "U3") (pin "9") (pinfunction "3A_9") (pintype "bidirectional"))
      (node (ref "X2") (pin "5") (pinfunction "5_5") (pintype "passive"))
    )
    (net (code "21") (name "/IN_CAM2_5V_TOL_PULLUP") (class "Default")
      (node (ref "R14") (pin "2") (pinfunction "2_2") (pintype "passive"))
      (node (ref "U3") (pin "12") (pinfunction "4A_12") (pintype "bidirectional"))
      (node (ref "X2") (pin "6") (pinfunction "6_6") (pintype "passive"))
    )
    (net (code "22") (name "/LED_CAM1") (class "Default")
      (node (ref "IC6") (pin "3") (pinfunction "PA7/ADC7/AC0-OUT_3") (pintype "bidirectional"))
      (node (ref "R24") (pin "1") (pinfunction "1_1") (pintype "passive"))
    )
    (net (code "23") (name "/LED_CAM2") (class "Default")
      (node (ref "IC6") (pin "17") (pinfunction "PC7/SCK/TXD1/CLKO/EVO_17") (pintype "bidirectional"))
      (node (ref "R25") (pin "1") (pinfunction "1_1") (pintype "passive"))
    )
    (net (code "24") (name "/LED_PWR") (class "Default")
      (node (ref "IC6") (pin "36") (pinfunction "PR0/XTAL2_36") (pintype "bidirectional"))
      (node (ref "R28") (pin "1") (pinfunction "1_1") (pintype "passive"))
    )
    (net (code "25") (name "/LED_STATE") (class "Default")
      (node (ref "IC6") (pin "25") (pinfunction "~XCK1MOSIPD5_25") (pintype "bidirectional"))
      (node (ref "R29") (pin "1") (pinfunction "1_1") (pintype "passive"))
    )
    (net (code "26") (name "/OUT_BNC_1") (class "Default")
      (node (ref "R18") (pin "1") (pinfunction "1_1") (pintype "passive"))
      (node (ref "X3") (pin "1") (pinfunction "1_1") (pintype "passive"))
    )
    (net (code "27") (name "/OUT_BNC_1_5V") (class "Default")
      (node (ref "R18") (pin "2") (pinfunction "2_2") (pintype "passive"))
      (node (ref "U5") (pin "8") (pinfunction "3Y_8") (pintype "bidirectional"))
    )
    (net (code "28") (name "/OUT_BNC_2") (class "Default")
      (node (ref "R19") (pin "1") (pinfunction "1_1") (pintype "passive"))
      (node (ref "X4") (pin "1") (pinfunction "1_1") (pintype "passive"))
    )
    (net (code "29") (name "/OUT_BNC_2_5V") (class "Default")
      (node (ref "R19") (pin "2") (pinfunction "2_2") (pintype "passive"))
      (node (ref "U5") (pin "11") (pinfunction "4Y_11") (pintype "bidirectional"))
    )
    (net (code "30") (name "/OUT_CAM1_TRIGGER_3V3") (class "Default")
      (node (ref "IC2") (pin "4") (pinfunction "O_4") (pintype "tri_state"))
      (node (ref "U2") (pin "3") (pinfunction "1Y_3") (pintype "bidirectional"))
      (node (ref "U5") (pin "2") (pinfunction "1A_2") (pintype "bidirectional"))
      (node (ref "X1") (pin "4") (pinfunction "4_4") (pintype "passive"))
    )
    (net (code "31") (name "/OUT_CAM1_TRIGGER_5V") (class "Default")
      (node (ref "U5") (pin "3") (pinfunction "1Y_3") (pintype "bidirectional"))
      (node (ref "X1") (pin "3") (pinfunction "3_3") (pintype "passive"))
    )
    (net (code "32") (name "/OUT_CAM2_TRIGGER_3V3") (class "Default")
      (node (ref "IC3") (pin "4") (pinfunction "O_4") (pintype "tri_state"))
      (node (ref "U2") (pin "6") (pinfunction "2Y_6") (pintype "bidirectional"))
      (node (ref "U5") (pin "5") (pinfunction "2A_5") (pintype "bidirectional"))
      (node (ref "X2") (pin "4") (pinfunction "4_4") (pintype "passive"))
    )
    (net (code "33") (name "/OUT_CAM2_TRIGGER_5V") (class "Default")
      (node (ref "U5") (pin "6") (pinfunction "2Y_6") (pintype "bidirectional"))
      (node (ref "X2") (pin "3") (pinfunction "3_3") (pintype "passive"))
    )
    (net (code "34") (name "/PDI_CLK") (class "Default")
      (node (ref "C37") (pin "1") (pinfunction "1_1") (pintype "passive"))
      (node (ref "IC6") (pin "35") (pinfunction "RESET/PDI-CLK_35") (pintype "input"))
      (node (ref "R34") (pin "1") (pinfunction "1_1") (pintype "passive"))
      (node (ref "SV1") (pin "5") (pinfunction "5_5") (pintype "passive"))
    )
    (net (code "35") (name "/PDI_DATA") (class "Default")
      (node (ref "IC6") (pin "34") (pinfunction "PDI-DATA_34") (pintype "bidirectional"))
      (node (ref "SV1") (pin "1") (pinfunction "1_1") (pintype "passive"))
    )
    (net (code "36") (name "/U_BNC3_BNC1_CASCADE_ENBL") (class "Default")
      (node (ref "IC6") (pin "4") (pinfunction "PB0/ADC8/AREF_4") (pintype "bidirectional"))
      (node (ref "U4") (pin "10") (pinfunction "~{3OE}_10") (pintype "bidirectional"))
    )
    (net (code "37") (name "/U_BNC3_BNC2_CASCADE_ENBL") (class "Default")
      (node (ref "IC6") (pin "5") (pinfunction "PB1/ADC9_5") (pintype "bidirectional"))
      (node (ref "U4") (pin "13") (pinfunction "~{4OE}_13") (pintype "bidirectional"))
    )
    (net (code "38") (name "/U_BNC3_CASCADE_TO_CAM1_ENBL") (class "Default")
      (node (ref "IC6") (pin "1") (pinfunction "PA5/ADC5_1") (pintype "bidirectional"))
      (node (ref "U4") (pin "1") (pinfunction "~{1OE}_1") (pintype "bidirectional"))
    )
    (net (code "39") (name "/U_BNC3_CASCADE_TO_CAM2_ENBL") (class "Default")
      (node (ref "IC6") (pin "2") (pinfunction "PA6/ADC6_2") (pintype "bidirectional"))
      (node (ref "U4") (pin "4") (pinfunction "~{2OE}_4") (pintype "bidirectional"))
    )
    (net (code "40") (name "/U_CAM1_TRIGGER_INV_ENBL") (class "Default")
      (node (ref "IC2") (pin "1") (pinfunction "OE_1") (pintype "input"))
      (node (ref "IC6") (pin "43") (pinfunction "PA3/ADC3_43") (pintype "bidirectional"))
      (node (ref "R6") (pin "2") (pinfunction "2_2") (pintype "passive"))
    )
    (net (code "41") (name "/U_CAM1_TRIGGER_N-INV-ENBL") (class "Default")
      (node (ref "IC6") (pin "44") (pinfunction "PA4/ADC4_44") (pintype "bidirectional"))
      (node (ref "R4") (pin "2") (pinfunction "2_2") (pintype "passive"))
      (node (ref "U2") (pin "1") (pinfunction "~{1OE}_1") (pintype "bidirectional"))
    )
    (net (code "42") (name "/U_CAM2_TRIGGER_INV_ENBL") (class "Default")
      (node (ref "IC3") (pin "1") (pinfunction "OE_1") (pintype "input"))
      (node (ref "IC6") (pin "14") (pinfunction "PC4/OC1A/#SS_14") (pintype "bidirectional"))
      (node (ref "R7") (pin "2") (pinfunction "2_2") (pintype "passive"))
    )
    (net (code "43") (name "/U_CAM2_TRIGGER_N-INV_ENBL") (class "Default")
      (node (ref "IC6") (pin "15") (pinfunction "PC5/OC1B/MOSI/XCK1_15") (pintype "bidirectional"))
      (node (ref "R2") (pin "2") (pinfunction "2_2") (pintype "passive"))
      (node (ref "U2") (pin "4") (pinfunction "~{2OE}_4") (pintype "bidirectional"))
    )
    (net (code "44") (name "/U_IN_BNC_3_5V") (class "Default")
      (node (ref "IC6") (pin "7") (pinfunction "PB3/ADC11/DAC1_7") (pintype "bidirectional"))
      (node (ref "U2") (pin "11") (pinfunction "4Y_11") (pintype "bidirectional"))
    )
    (net (code "45") (name "/U_IN_CAM1_STROBE_5V") (class "Default")
      (node (ref "IC6") (pin "40") (pinfunction "PA0/ADC0/AREF_40") (pintype "bidirectional"))
      (node (ref "U3") (pin "3") (pinfunction "1Y_3") (pintype "bidirectional"))
    )
    (net (code "46") (name "/U_IN_CAM1_STROBE_PULLUP_5V") (class "Default")
      (node (ref "IC6") (pin "41") (pinfunction "PA1/ADC1_41") (pintype "bidirectional"))
      (node (ref "U3") (pin "6") (pinfunction "2Y_6") (pintype "bidirectional"))
    )
    (net (code "47") (name "/U_IN_CAM2_STROBE_5V") (class "Default")
      (node (ref "IC6") (pin "13") (pinfunction "PC3/OC0D/TXD0_13") (pintype "bidirectional"))
      (node (ref "U3") (pin "8") (pinfunction "3Y_8") (pintype "bidirectional"))
    )
    (net (code "48") (name "/U_IN_CAM2_STROBE_PULLUP_5V") (class "Default")
      (node (ref "IC6") (pin "12") (pinfunction "PC2/OC0C/RXD0_12") (pintype "bidirectional"))
      (node (ref "U3") (pin "11") (pinfunction "4Y_11") (pintype "bidirectional"))
    )
    (net (code "49") (name "/U_IO_CAM1_TRIGGER") (class "Default")
      (node (ref "IC2") (pin "2") (pinfunction "I_2") (pintype "input"))
      (node (ref "IC6") (pin "20") (pinfunction "~{OC0APD0}_20") (pintype "bidirectional"))
      (node (ref "R3") (pin "2") (pinfunction "2_2") (pintype "passive"))
      (node (ref "U2") (pin "2") (pinfunction "1A_2") (pintype "bidirectional"))
      (node (ref "U4") (pin "3") (pinfunction "1Y_3") (pintype "bidirectional"))
      (node (ref "U4") (pin "9") (pinfunction "3A_9") (pintype "bidirectional"))
    )
    (net (code "50") (name "/U_IO_CAM2_TRIGGER") (class "Default")
      (node (ref "IC3") (pin "2") (pinfunction "I_2") (pintype "input"))
      (node (ref "IC6") (pin "10") (pinfunction "PC0/OC0A/SDA_10") (pintype "bidirectional"))
      (node (ref "R5") (pin "2") (pinfunction "2_2") (pintype "passive"))
      (node (ref "U2") (pin "5") (pinfunction "2A_5") (pintype "bidirectional"))
      (node (ref "U4") (pin "12") (pinfunction "4A_12") (pintype "bidirectional"))
      (node (ref "U4") (pin "6") (pinfunction "2Y_6") (pintype "bidirectional"))
    )
    (net (code "51") (name "/U_OUT_BNC_1_5V") (class "Default")
      (node (ref "IC6") (pin "21") (pinfunction "~OC0BXCK0PD1_21") (pintype "bidirectional"))
      (node (ref "R10") (pin "1") (pinfunction "1_1") (pintype "passive"))
      (node (ref "U4") (pin "8") (pinfunction "3Y_8") (pintype "bidirectional"))
      (node (ref "U5") (pin "9") (pinfunction "3A_9") (pintype "bidirectional"))
    )
    (net (code "52") (name "/U_OUT_BNC_2_5V") (class "Default")
      (node (ref "IC6") (pin "11") (pinfunction "PC1/OC0B/XCK0/SCL_11") (pintype "bidirectional"))
      (node (ref "R11") (pin "1") (pinfunction "1_1") (pintype "passive"))
      (node (ref "U4") (pin "11") (pinfunction "4Y_11") (pintype "bidirectional"))
      (node (ref "U5") (pin "12") (pinfunction "4A_12") (pintype "bidirectional"))
    )
    (net (code "53") (name "/VREF") (class "Default")
      (node (ref "R12") (pin "1") (pinfunction "1_1") (pintype "passive"))
      (node (ref "R13") (pin "2") (pinfunction "2_2") (pintype "passive"))
      (node (ref "U1") (pin "12") (pinfunction "FB_12") (pintype "bidirectional"))
    )
    (net (code "54") (name "GND") (class "Default")
      (node (ref "C1") (pin "2") (pinfunction "2_2") (pintype "passive"))
      (node (ref "C10") (pin "2") (pinfunction "2_2") (pintype "passive"))
      (node (ref "C12") (pin "2") (pinfunction "2_2") (pintype "passive"))
      (node (ref "C13") (pin "2") (pinfunction "2_2") (pintype "passive"))
      (node (ref "C14") (pin "2") (pinfunction "2_2") (pintype "passive"))
      (node (ref "C15") (pin "2") (pinfunction "2_2") (pintype "passive"))
      (node (ref "C16") (pin "2") (pinfunction "2_2") (pintype "passive"))
      (node (ref "C17") (pin "-") (pinfunction "-_-") (pintype "passive"))
      (node (ref "C18") (pin "2") (pinfunction "2_2") (pintype "passive"))
      (node (ref "C19") (pin "2") (pinfunction "2_2") (pintype "passive"))
      (node (ref "C2") (pin "2") (pinfunction "2_2") (pintype "passive"))
      (node (ref "C20") (pin "2") (pinfunction "2_2") (pintype "passive"))
      (node (ref "C21") (pin "2") (pinfunction "2_2") (pintype "passive"))
      (node (ref "C22") (pin "2") (pinfunction "2_2") (pintype "passive"))
      (node (ref "C23") (pin "2") (pinfunction "2_2") (pintype "passive"))
      (node (ref "C24") (pin "2") (pinfunction "2_2") (pintype "passive"))
      (node (ref "C25") (pin "2") (pinfunction "2_2") (pintype "passive"))
      (node (ref "C26") (pin "2") (pinfunction "2_2") (pintype "passive"))
      (node (ref "C27") (pin "2") (pinfunction "2_2") (pintype "passive"))
      (node (ref "C28") (pin "2") (pinfunction "2_2") (pintype "passive"))
      (node (ref "C29") (pin "2") (pinfunction "2_2") (pintype "passive"))
      (node (ref "C3") (pin "2") (pinfunction "2_2") (pintype "passive"))
      (node (ref "C30") (pin "2") (pinfunction "2_2") (pintype "passive"))
      (node (ref "C31") (pin "2") (pinfunction "2_2") (pintype "passive"))
      (node (ref "C32") (pin "2") (pinfunction "2_2") (pintype "passive"))
      (node (ref "C33") (pin "2") (pinfunction "2_2") (pintype "passive"))
      (node (ref "C34") (pin "2") (pinfunction "2_2") (pintype "passive"))
      (node (ref "C35") (pin "2") (pinfunction "2_2") (pintype "passive"))
      (node (ref "C36") (pin "2") (pinfunction "2_2") (pintype "passive"))
      (node (ref "C37") (pin "2") (pinfunction "2_2") (pintype "passive"))
      (node (ref "C4") (pin "2") (pinfunction "2_2") (pintype "passive"))
      (node (ref "C5") (pin "2") (pinfunction "2_2") (pintype "passive"))
      (node (ref "C6") (pin "2") (pinfunction "2_2") (pintype "passive"))
      (node (ref "C7") (pin "-") (pinfunction "-_-") (pintype "passive"))
      (node (ref "C8") (pin "2") (pinfunction "2_2") (pintype "passive"))
      (node (ref "C9") (pin "2") (pinfunction "2_2") (pintype "passive"))
      (node (ref "CLOCK_IN") (pin "5") (pinfunction "5_5") (pintype "passive"))
      (node (ref "D1") (pin "A") (pinfunction "A_A") (pintype "passive"))
      (node (ref "GND1_TP") (pin "TP") (pinfunction "TP_TP") (pintype "input"))
      (node (ref "GND2_TP") (pin "TP") (pinfunction "TP_TP") (pintype "input"))
      (node (ref "IC1") (pin "P$2") (pinfunction "GND_P$2") (pintype "bidirectional"))
      (node (ref "IC10") (pin "4") (pinfunction "AGND_4") (pintype "bidirectional"))
      (node (ref "IC2") (pin "3") (pinfunction "GND_3") (pintype "power_in"))
      (node (ref "IC3") (pin "3") (pinfunction "GND_3") (pintype "power_in"))
      (node (ref "IC4") (pin "18") (pinfunction "GND_18") (pintype "power_in"))
      (node (ref "IC4") (pin "21") (pinfunction "GND_21") (pintype "power_in"))
      (node (ref "IC4") (pin "25") (pinfunction "GND_25") (pintype "power_in"))
      (node (ref "IC4") (pin "26") (pinfunction "TEST_26") (pintype "input"))
      (node (ref "IC4") (pin "7") (pinfunction "GND_7") (pintype "power_in"))
      (node (ref "IC5") (pin "2") (pinfunction "GND_2") (pintype "bidirectional"))
      (node (ref "IC6") (pin "18") (pinfunction "GND_18") (pintype "power_in"))
      (node (ref "IC6") (pin "30") (pinfunction "GND_30") (pintype "power_in"))
      (node (ref "IC6") (pin "38") (pinfunction "GND_38") (pintype "power_in"))
      (node (ref "IC6") (pin "8") (pinfunction "GND_8") (pintype "power_in"))
      (node (ref "IC7") (pin "3") (pinfunction "GND_3") (pintype "power_in"))
      (node (ref "IC8") (pin "3") (pinfunction "GND_3") (pintype "power_in"))
      (node (ref "IC9") (pin "2") (pinfunction "GND_2") (pintype "bidirectional"))
      (node (ref "OSC1") (pin "P$2") (pinfunction "GND_P$2") (pintype "passive"))
      (node (ref "PWR1") (pin "P2") (pinfunction "2_P2") (pintype "passive"))
      (node (ref "PWR1") (pin "P3") (pinfunction "3_P3") (pintype "passive"))
      (node (ref "R1") (pin "2") (pinfunction "2_2") (pintype "passive"))
      (node (ref "R10") (pin "2") (pinfunction "2_2") (pintype "passive"))
      (node (ref "R11") (pin "2") (pinfunction "2_2") (pintype "passive"))
      (node (ref "R13") (pin "1") (pinfunction "1_1") (pintype "passive"))
      (node (ref "R15") (pin "1") (pinfunction "1_1") (pintype "passive"))
      (node (ref "R17") (pin "1") (pinfunction "1_1") (pintype "passive"))
      (node (ref "R2") (pin "1") (pinfunction "1_1") (pintype "passive"))
      (node (ref "R21") (pin "1") (pinfunction "1_1") (pintype "passive"))
      (node (ref "R22") (pin "2") (pinfunction "2_2") (pintype "passive"))
      (node (ref "R23") (pin "2") (pinfunction "2_2") (pintype "passive"))
      (node (ref "R3") (pin "1") (pinfunction "1_1") (pintype "passive"))
      (node (ref "R32") (pin "2") (pinfunction "2_2") (pintype "passive"))
      (node (ref "R4") (pin "1") (pinfunction "1_1") (pintype "passive"))
      (node (ref "R5") (pin "1") (pinfunction "1_1") (pintype "passive"))
      (node (ref "SV1") (pin "6") (pinfunction "6_6") (pintype "passive"))
      (node (ref "T1") (pin "2") (pinfunction "E_2") (pintype "passive"))
      (node (ref "T2") (pin "2") (pinfunction "E_2") (pintype "passive"))
      (node (ref "T3") (pin "2") (pinfunction "E_2") (pintype "passive"))
      (node (ref "T4") (pin "2") (pinfunction "E_2") (pintype "passive"))
      (node (ref "U1") (pin "1") (pinfunction "GND_1") (pintype "bidirectional"))
      (node (ref "U1") (pin "14") (pinfunction "SYNC_14") (pintype "bidirectional"))
      (node (ref "U1") (pin "16") (pinfunction "GND_16") (pintype "bidirectional"))
      (node (ref "U1") (pin "17") (pinfunction "GND_17") (pintype "bidirectional"))
      (node (ref "U1") (pin "8") (pinfunction "GND_8") (pintype "bidirectional"))
      (node (ref "U1") (pin "9") (pinfunction "GND_9") (pintype "bidirectional"))
      (node (ref "U2") (pin "13") (pinfunction "~{4OE}_13") (pintype "bidirectional"))
      (node (ref "U2") (pin "7") (pinfunction "GND_7") (pintype "bidirectional"))
      (node (ref "U3") (pin "1") (pinfunction "~{1OE}_1") (pintype "bidirectional"))
      (node (ref "U3") (pin "10") (pinfunction "~{3OE}_10") (pintype "bidirectional"))
      (node (ref "U3") (pin "13") (pinfunction "~{4OE}_13") (pintype "bidirectional"))
      (node (ref "U3") (pin "4") (pinfunction "~{2OE}_4") (pintype "bidirectional"))
      (node (ref "U3") (pin "7") (pinfunction "GND_7") (pintype "bidirectional"))
      (node (ref "U4") (pin "7") (pinfunction "GND_7") (pintype "bidirectional"))
      (node (ref "U5") (pin "1") (pinfunction "~{1OE}_1") (pintype "bidirectional"))
      (node (ref "U5") (pin "10") (pinfunction "~{3OE}_10") (pintype "bidirectional"))
      (node (ref "U5") (pin "13") (pinfunction "~{4OE}_13") (pintype "bidirectional"))
      (node (ref "U5") (pin "4") (pinfunction "~{2OE}_4") (pintype "bidirectional"))
      (node (ref "U5") (pin "7") (pinfunction "GND_7") (pintype "bidirectional"))
      (node (ref "USB1") (pin "P$5") (pinfunction "5_P$5") (pintype "bidirectional"))
      (node (ref "X1") (pin "2") (pinfunction "2_2") (pintype "passive"))
      (node (ref "X1") (pin "7") (pinfunction "7_7") (pintype "passive"))
      (node (ref "X2") (pin "2") (pinfunction "2_2") (pintype "passive"))
      (node (ref "X2") (pin "7") (pinfunction "7_7") (pintype "passive"))
      (node (ref "X3") (pin "2") (pinfunction "2_2") (pintype "passive"))
      (node (ref "X3") (pin "3") (pinfunction "2_3") (pintype "passive"))
      (node (ref "X4") (pin "2") (pinfunction "2_2") (pintype "passive"))
      (node (ref "X4") (pin "3") (pinfunction "2_3") (pintype "passive"))
      (node (ref "X5") (pin "2") (pinfunction "2_2") (pintype "passive"))
      (node (ref "X5") (pin "3") (pinfunction "2_3") (pintype "passive"))
    )
    (net (code "55") (name "Net-(C11-Pad2)") (class "Default")
      (node (ref "C11") (pin "2") (pinfunction "2_2") (pintype "passive"))
      (node (ref "D1") (pin "C") (pinfunction "C_C") (pintype "passive"))
      (node (ref "L1") (pin "2") (pinfunction "2_2") (pintype "passive"))
      (node (ref "U1") (pin "5") (pinfunction "SW_5") (pintype "bidirectional"))
      (node (ref "U1") (pin "6") (pinfunction "SW_6") (pintype "bidirectional"))
    )
    (net (code "56") (name "Net-(CLOCK_IN-Pad1)") (class "Default")
      (node (ref "CLOCK_IN") (pin "1") (pinfunction "1_1") (pintype "passive"))
      (node (ref "R35") (pin "2") (pinfunction "2_2") (pintype "passive"))
      (node (ref "R36") (pin "1") (pinfunction "1_1") (pintype "passive"))
    )
    (net (code "57") (name "Net-(IC4-3V3OUT)") (class "Default")
      (node (ref "C14") (pin "1") (pinfunction "1_1") (pintype "passive"))
      (node (ref "IC4") (pin "17") (pinfunction "3V3OUT_17") (pintype "output"))
    )
    (net (code "58") (name "Net-(IC4-USBDM)") (class "Default")
      (node (ref "C13") (pin "1") (pinfunction "1_1") (pintype "passive"))
      (node (ref "IC1") (pin "P$6") (pinfunction "IO1_P$6") (pintype "bidirectional"))
      (node (ref "IC4") (pin "16") (pinfunction "USBDM_16") (pintype "bidirectional"))
    )
    (net (code "59") (name "Net-(IC4-USBDP)") (class "Default")
      (node (ref "C10") (pin "1") (pinfunction "1_1") (pintype "passive"))
      (node (ref "IC1") (pin "P$4") (pinfunction "IO2_P$4") (pintype "bidirectional"))
      (node (ref "IC4") (pin "15") (pinfunction "USBDP_15") (pintype "bidirectional"))
    )
    (net (code "60") (name "Net-(IC6-PR1{slash}XTAL1)") (class "Default")
      (node (ref "IC6") (pin "37") (pinfunction "PR1/XTAL1_37") (pintype "bidirectional"))
      (node (ref "OSC1") (pin "P$3") (pinfunction "OUTPUT_P$3") (pintype "passive"))
    )
    (net (code "61") (name "Net-(IC9-OUT)") (class "Default")
      (node (ref "C35") (pin "1") (pinfunction "1_1") (pintype "passive"))
      (node (ref "C36") (pin "1") (pinfunction "1_1") (pintype "passive"))
      (node (ref "IC9") (pin "5") (pinfunction "OUT_5") (pintype "bidirectional"))
      (node (ref "R35") (pin "1") (pinfunction "1_1") (pintype "passive"))
    )
    (net (code "62") (name "Net-(IC10-A1)") (class "Default")
      (node (ref "IC10") (pin "2") (pinfunction "A1_2") (pintype "bidirectional"))
      (node (ref "IC7") (pin "4") (pinfunction "O_4") (pintype "tri_state"))
      (node (ref "IC8") (pin "4") (pinfunction "O_4") (pintype "tri_state"))
    )
    (net (code "63") (name "Net-(IC10-B1)") (class "Default")
      (node (ref "CLOCK_OUT") (pin "4") (pinfunction "4_4") (pintype "passive"))
      (node (ref "IC10") (pin "6") (pinfunction "B1_6") (pintype "bidirectional"))
    )
    (net (code "64") (name "Net-(IC10-BGND)") (class "Default")
      (node (ref "C38") (pin "2") (pinfunction "2_2") (pintype "passive"))
      (node (ref "CLOCK_OUT") (pin "5") (pinfunction "5_5") (pintype "passive"))
      (node (ref "IC10") (pin "5") (pinfunction "BGND_5") (pintype "bidirectional"))
    )
    (net (code "65") (name "Net-(IC10-BVDD)") (class "Default")
      (node (ref "C38") (pin "1") (pinfunction "1_1") (pintype "passive"))
      (node (ref "CLOCK_OUT") (pin "1") (pinfunction "1_1") (pintype "passive"))
      (node (ref "IC10") (pin "8") (pinfunction "BVDD_8") (pintype "bidirectional"))
    )
    (net (code "66") (name "Net-(LED1A-C)") (class "Default")
      (node (ref "LED1") (pin "C1") (pinfunction "C_C1") (pintype "passive"))
      (node (ref "R27") (pin "1") (pinfunction "1_1") (pintype "passive"))
    )
    (net (code "67") (name "Net-(LED1B-C)") (class "Default")
      (node (ref "LED1") (pin "C2") (pinfunction "C_C2") (pintype "passive"))
      (node (ref "R26") (pin "1") (pinfunction "1_1") (pintype "passive"))
    )
    (net (code "68") (name "Net-(LED2A-C)") (class "Default")
      (node (ref "LED2") (pin "C1") (pinfunction "C_C1") (pintype "passive"))
      (node (ref "R31") (pin "1") (pinfunction "1_1") (pintype "passive"))
    )
    (net (code "69") (name "Net-(LED2B-C)") (class "Default")
      (node (ref "LED2") (pin "C2") (pinfunction "C_C2") (pintype "passive"))
      (node (ref "R30") (pin "1") (pinfunction "1_1") (pintype "passive"))
    )
    (net (code "70") (name "Net-(T1-B)") (class "Default")
      (node (ref "R24") (pin "2") (pinfunction "2_2") (pintype "passive"))
      (node (ref "T1") (pin "1") (pinfunction "B_1") (pintype "passive"))
    )
    (net (code "71") (name "Net-(T1-C)") (class "Default")
      (node (ref "R26") (pin "2") (pinfunction "2_2") (pintype "passive"))
      (node (ref "T1") (pin "3") (pinfunction "C_3") (pintype "passive"))
    )
    (net (code "72") (name "Net-(T2-B)") (class "Default")
      (node (ref "R25") (pin "2") (pinfunction "2_2") (pintype "passive"))
      (node (ref "T2") (pin "1") (pinfunction "B_1") (pintype "passive"))
    )
    (net (code "73") (name "Net-(T2-C)") (class "Default")
      (node (ref "R27") (pin "2") (pinfunction "2_2") (pintype "passive"))
      (node (ref "T2") (pin "3") (pinfunction "C_3") (pintype "passive"))
    )
    (net (code "74") (name "Net-(T3-B)") (class "Default")
      (node (ref "R28") (pin "2") (pinfunction "2_2") (pintype "passive"))
      (node (ref "T3") (pin "1") (pinfunction "B_1") (pintype "passive"))
    )
    (net (code "75") (name "Net-(T3-C)") (class "Default")
      (node (ref "R30") (pin "2") (pinfunction "2_2") (pintype "passive"))
      (node (ref "T3") (pin "3") (pinfunction "C_3") (pintype "passive"))
    )
    (net (code "76") (name "Net-(T4-B)") (class "Default")
      (node (ref "R29") (pin "2") (pinfunction "2_2") (pintype "passive"))
      (node (ref "T4") (pin "1") (pinfunction "B_1") (pintype "passive"))
    )
    (net (code "77") (name "Net-(T4-C)") (class "Default")
      (node (ref "R31") (pin "2") (pinfunction "2_2") (pintype "passive"))
      (node (ref "T4") (pin "3") (pinfunction "C_3") (pintype "passive"))
    )
    (net (code "78") (name "Net-(U1-BOOST)") (class "Default")
      (node (ref "C11") (pin "1") (pinfunction "1_1") (pintype "passive"))
      (node (ref "D2") (pin "C") (pinfunction "C_C") (pintype "passive"))
      (node (ref "U1") (pin "2") (pinfunction "BOOST_2") (pintype "bidirectional"))
    )
    (net (code "79") (name "Net-(U2-~{3OE})") (class "Default")
      (node (ref "R8") (pin "2") (pinfunction "2_2") (pintype "passive"))
      (node (ref "U2") (pin "10") (pinfunction "~{3OE}_10") (pintype "bidirectional"))
    )
    (net (code "80") (name "Net-(USB1-2)") (class "Default")
      (node (ref "IC1") (pin "P$1") (pinfunction "IO1_P$1") (pintype "bidirectional"))
      (node (ref "USB1") (pin "P$2") (pinfunction "2_P$2") (pintype "bidirectional"))
    )
    (net (code "81") (name "Net-(USB1-3)") (class "Default")
      (node (ref "IC1") (pin "P$3") (pinfunction "IO2_P$3") (pintype "bidirectional"))
      (node (ref "USB1") (pin "P$3") (pinfunction "3_P$3") (pintype "bidirectional"))
    )
    (net (code "82") (name "Net-(USB1-P$1)") (class "Default")
      (node (ref "R1") (pin "1") (pinfunction "1_1") (pintype "passive"))
      (node (ref "USB1") (pin "SHIELD_1") (pinfunction "P$1_SHIELD_1") (pintype "bidirectional"))
    )
    (net (code "83") (name "Net-(USB1-P$4)") (class "Default")
      (node (ref "C1") (pin "1") (pinfunction "1_1") (pintype "passive"))
      (node (ref "USB1") (pin "SHIELD_4") (pinfunction "P$4_SHIELD_4") (pintype "bidirectional"))
    )
    (net (code "84") (name "V+") (class "Default")
      (node (ref "C17") (pin "+") (pinfunction "+_+") (pintype "passive"))
      (node (ref "C18") (pin "1") (pinfunction "1_1") (pintype "passive"))
      (node (ref "D2") (pin "A") (pinfunction "A_A") (pintype "passive"))
      (node (ref "L1") (pin "1") (pinfunction "1_1") (pintype "passive"))
      (node (ref "R12") (pin "2") (pinfunction "2_2") (pintype "passive"))
      (node (ref "X1") (pin "8") (pinfunction "8_8") (pintype "passive"))
      (node (ref "X2") (pin "8") (pinfunction "8_8") (pintype "passive"))
    )
    (net (code "85") (name "unconnected-(IC4-CBUS0-Pad23)") (class "Default")
      (node (ref "IC4") (pin "23") (pinfunction "CBUS0_23") (pintype "passive"))
    )
    (net (code "86") (name "unconnected-(IC4-CBUS1-Pad22)") (class "Default")
      (node (ref "IC4") (pin "22") (pinfunction "CBUS1_22") (pintype "passive"))
    )
    (net (code "87") (name "unconnected-(IC4-CBUS2-Pad13)") (class "Default")
      (node (ref "IC4") (pin "13") (pinfunction "CBUS2_13") (pintype "passive"))
    )
    (net (code "88") (name "unconnected-(IC4-CBUS3-Pad14)") (class "Default")
      (node (ref "IC4") (pin "14") (pinfunction "CBUS3_14") (pintype "passive"))
    )
    (net (code "89") (name "unconnected-(IC4-CBUS4-Pad12)") (class "Default")
      (node (ref "IC4") (pin "12") (pinfunction "CBUS4_12") (pintype "passive"))
    )
    (net (code "90") (name "unconnected-(IC4-OSCI-Pad27)") (class "Default")
      (node (ref "IC4") (pin "27") (pinfunction "OSCI_27") (pintype "passive"))
    )
    (net (code "91") (name "unconnected-(IC4-OSCO-Pad28)") (class "Default")
      (node (ref "IC4") (pin "28") (pinfunction "OSCO_28") (pintype "output"))
    )
    (net (code "92") (name "unconnected-(IC4-~{DCD}-Pad10)") (class "Default")
      (node (ref "IC4") (pin "10") (pinfunction "~{DCD}_10") (pintype "passive"))
    )
    (net (code "93") (name "unconnected-(IC4-~{DSR}-Pad9)") (class "Default")
      (node (ref "IC4") (pin "9") (pinfunction "~{DSR}_9") (pintype "passive"))
    )
    (net (code "94") (name "unconnected-(IC4-~{DTR}-Pad2)") (class "Default")
      (node (ref "IC4") (pin "2") (pinfunction "~{DTR}_2") (pintype "passive"))
    )
    (net (code "95") (name "unconnected-(IC4-~{RESET}-Pad19)") (class "Default")
      (node (ref "IC4") (pin "19") (pinfunction "~{RESET}_19") (pintype "passive"))
    )
    (net (code "96") (name "unconnected-(IC4-~{RI}-Pad6)") (class "Default")
      (node (ref "IC4") (pin "6") (pinfunction "~{RI}_6") (pintype "passive"))
    )
    (net (code "97") (name "unconnected-(IC5-N{slash}C-Pad4)") (class "Default")
      (node (ref "IC5") (pin "4") (pinfunction "N/C_4") (pintype "bidirectional"))
    )
    (net (code "98") (name "unconnected-(IC6-PA2{slash}ADC2-Pad42)") (class "Default")
      (node (ref "IC6") (pin "42") (pinfunction "PA2/ADC2_42") (pintype "bidirectional"))
    )
    (net (code "99") (name "unconnected-(IC6-PC6{slash}MISO{slash}RXD1-Pad16)") (class "Default")
      (node (ref "IC6") (pin "16") (pinfunction "PC6/MISO/RXD1_16") (pintype "bidirectional"))
    )
    (net (code "100") (name "unconnected-(IC9-N{slash}C-Pad4)") (class "Default")
      (node (ref "IC9") (pin "4") (pinfunction "N/C_4") (pintype "bidirectional"))
    )
    (net (code "101") (name "unconnected-(IC10-AVDD{slash}NC-Pad3)") (class "Default")
      (node (ref "IC10") (pin "3") (pinfunction "AVDD/NC_3") (pintype "bidirectional"))
    )
    (net (code "102") (name "unconnected-(IC10-BGND{slash}NC-Pad7)") (class "Default")
      (node (ref "IC10") (pin "7") (pinfunction "BGND/NC_7") (pintype "bidirectional"))
    )
    (net (code "103") (name "unconnected-(OSC1-STANDBY#-PadP$1)") (class "Default")
      (node (ref "OSC1") (pin "P$1") (pinfunction "STANDBY#_P$1") (pintype "passive"))
    )
    (net (code "104") (name "unconnected-(SV1-Pad3)") (class "Default")
      (node (ref "SV1") (pin "3") (pinfunction "3_3") (pintype "passive"))
    )
    (net (code "105") (name "unconnected-(SV1-Pad4)") (class "Default")
      (node (ref "SV1") (pin "4") (pinfunction "4_4") (pintype "passive"))
    )
    (net (code "106") (name "unconnected-(U1-NC7-Pad7)") (class "Default")
      (node (ref "U1") (pin "7") (pinfunction "NC7_7") (pintype "bidirectional"))
    )
    (net (code "107") (name "unconnected-(U1-NC10-Pad10)") (class "Default")
      (node (ref "U1") (pin "10") (pinfunction "NC10_10") (pintype "bidirectional"))
    )
    (net (code "108") (name "unconnected-(U1-NC15-Pad15)") (class "Default")
      (node (ref "U1") (pin "15") (pinfunction "NC15_15") (pintype "bidirectional"))
    )
    (net (code "109") (name "unconnected-(U1-VC-Pad13)") (class "Default")
      (node (ref "U1") (pin "13") (pinfunction "VC_13") (pintype "bidirectional"))
    )
    (net (code "110") (name "unconnected-(U1-~{SHDN}-Pad11)") (class "Default")
      (node (ref "U1") (pin "11") (pinfunction "~{SHDN}_11") (pintype "bidirectional"))
    )
    (net (code "111") (name "unconnected-(U2-3A-Pad9)") (class "Default")
      (node (ref "U2") (pin "9") (pinfunction "3A_9") (pintype "bidirectional"))
    )
    (net (code "112") (name "unconnected-(U2-3Y-Pad8)") (class "Default")
      (node (ref "U2") (pin "8") (pinfunction "3Y_8") (pintype "bidirectional"))
    )
    (net (code "113") (name "unconnected-(USB1-4-PadP$4)") (class "Default")
      (node (ref "USB1") (pin "P$4") (pinfunction "4_P$4") (pintype "bidirectional"))
    )
    (net (code "114") (name "unconnected-(USB1-P$2-PadSHIELD_2)") (class "Default")
      (node (ref "USB1") (pin "SHIELD_2") (pinfunction "P$2_SHIELD_2") (pintype "bidirectional"))
    )
    (net (code "115") (name "unconnected-(USB1-P$3-PadSHIELD_3)") (class "Default")
      (node (ref "USB1") (pin "SHIELD_3") (pinfunction "P$3_SHIELD_3") (pintype "bidirectional"))
    )
  )
)
